# eggbothat3.net
KiCad netlist of a schematic drawn in EAGLE
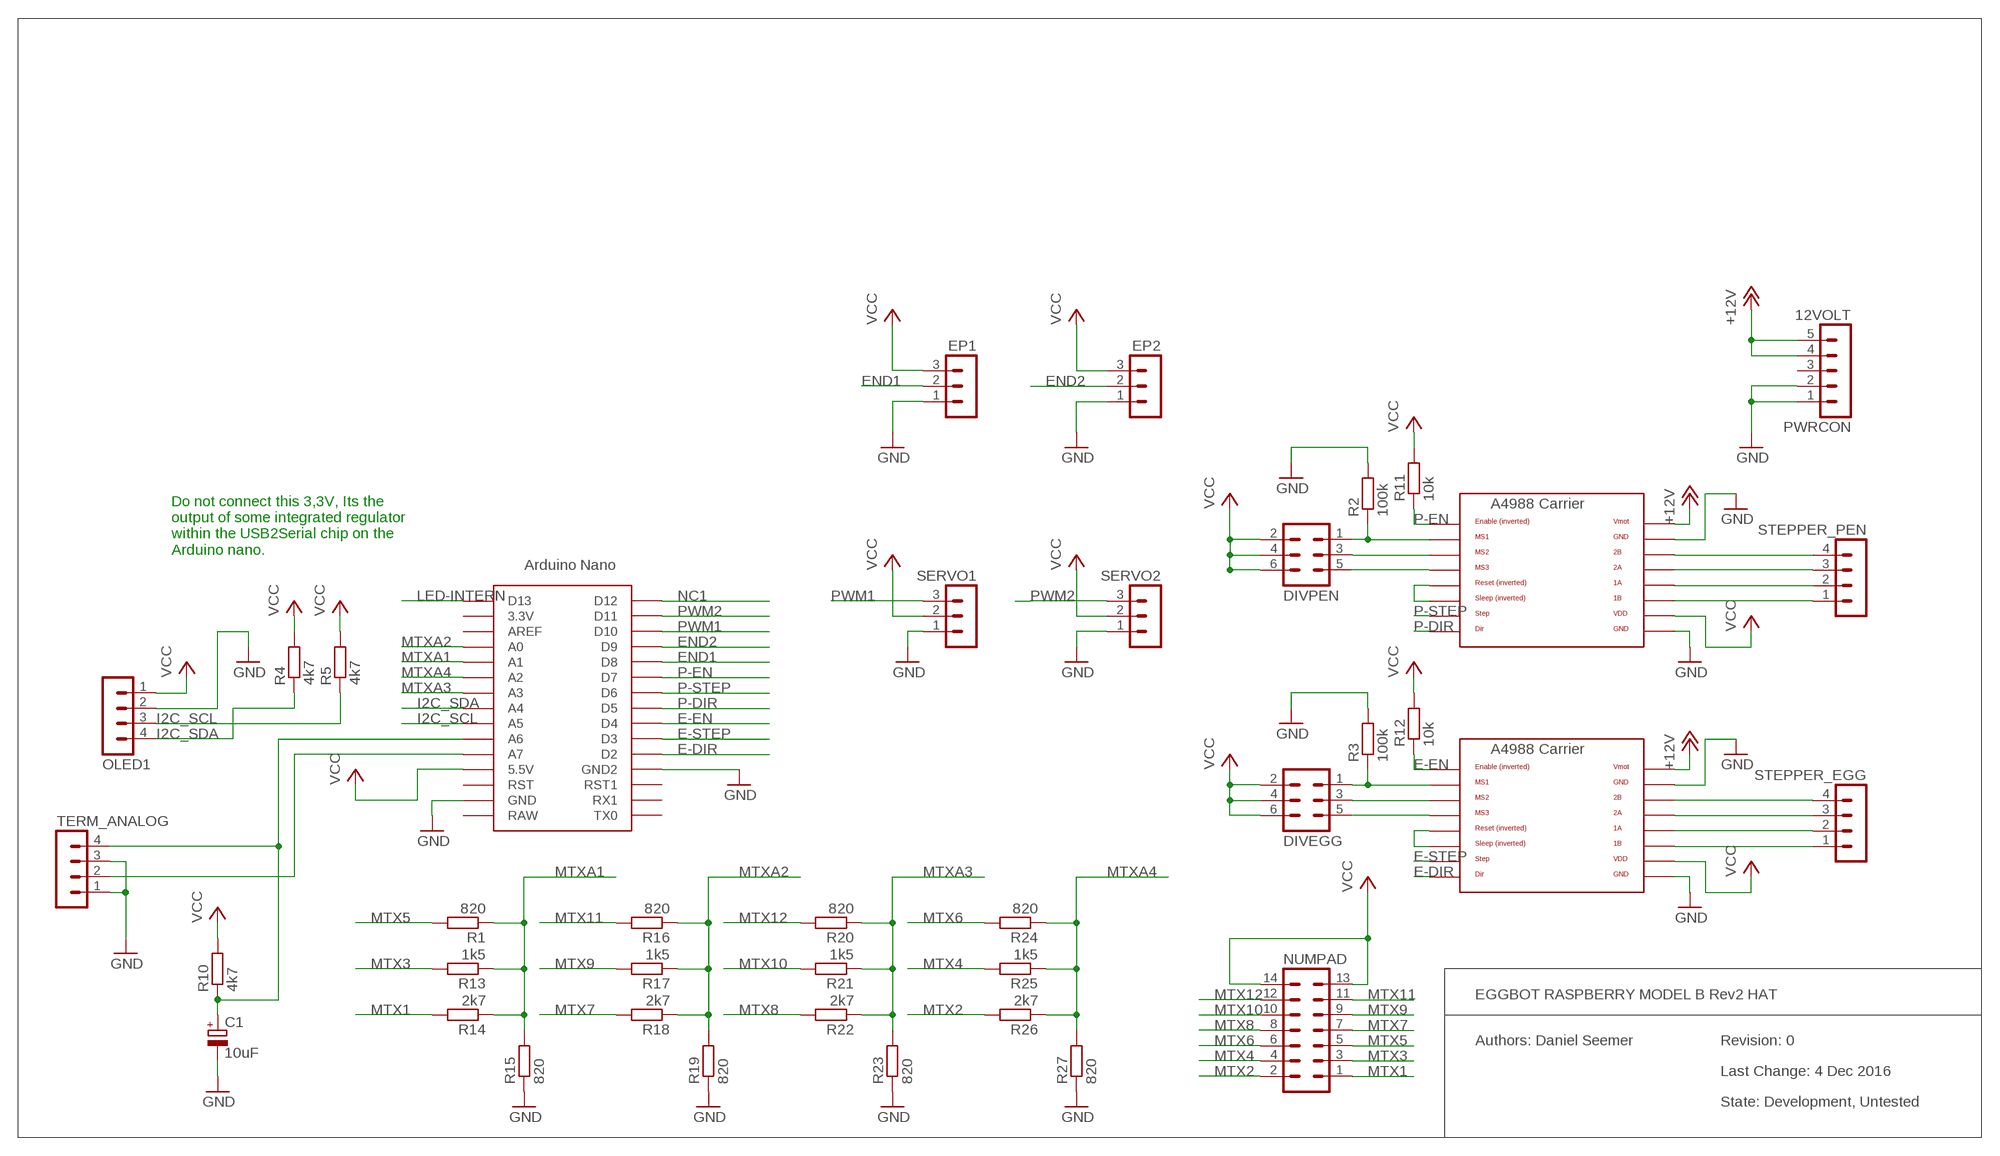
[diagram p0: schematic, sheet 1]

(export (version "E")
  (design (tool "Eeschema 10.0.6"))
  (components
    (comp (ref "12VOLT")
      (value "PWRCON")
      (footprint "eagle-import:MA05-1")
      (libsource (lib "eagle-import") (part "MA05-1"))
    )
    (comp (ref "C1")
      (value "10uF")
      (footprint "eagle-import:E2,5-5")
      (libsource (lib "eagle-import") (part "CPOL-EUE2.5-5"))
    )
    (comp (ref "DIVEGG")
      (value "MA03-2")
      (footprint "eagle-import:MA03-2")
      (libsource (lib "eagle-import") (part "MA03-2"))
    )
    (comp (ref "DIVPEN")
      (value "MA03-2")
      (footprint "eagle-import:MA03-2")
      (libsource (lib "eagle-import") (part "MA03-2"))
    )
    (comp (ref "EP1")
      (value "MA03-1")
      (footprint "eagle-import:MA03-1")
      (libsource (lib "eagle-import") (part "MA03-1"))
    )
    (comp (ref "EP2")
      (value "MA03-1")
      (footprint "eagle-import:MA03-1")
      (libsource (lib "eagle-import") (part "MA03-1"))
    )
    (comp (ref "NUMPAD")
      (value "MA07-2")
      (footprint "eagle-import:MA07-2")
      (libsource (lib "eagle-import") (part "MA07-2"))
    )
    (comp (ref "OLED1")
      (value "MA04-1")
      (footprint "eagle-import:MA04-1")
      (libsource (lib "eagle-import") (part "MA04-1"))
    )
    (comp (ref "R1")
      (value "820")
      (footprint "eagle-import:R1206")
      (libsource (lib "eagle-import") (part "R-EU_R1206"))
    )
    (comp (ref "R2")
      (value "100k")
      (footprint "eagle-import:R1206")
      (libsource (lib "eagle-import") (part "R-EU_R1206"))
    )
    (comp (ref "R3")
      (value "100k")
      (footprint "eagle-import:R1206")
      (libsource (lib "eagle-import") (part "R-EU_R1206"))
    )
    (comp (ref "R4")
      (value "4k7")
      (footprint "eagle-import:R1206")
      (libsource (lib "eagle-import") (part "R-EU_R1206"))
    )
    (comp (ref "R5")
      (value "4k7")
      (footprint "eagle-import:R1206")
      (libsource (lib "eagle-import") (part "R-EU_R1206"))
    )
    (comp (ref "R10")
      (value "4k7")
      (footprint "eagle-import:R1206")
      (libsource (lib "eagle-import") (part "R-EU_R1206"))
    )
    (comp (ref "R11")
      (value "10k")
      (footprint "eagle-import:R1206")
      (libsource (lib "eagle-import") (part "R-EU_R1206"))
    )
    (comp (ref "R12")
      (value "10k")
      (footprint "eagle-import:R1206")
      (libsource (lib "eagle-import") (part "R-EU_R1206"))
    )
    (comp (ref "R13")
      (value "1k5")
      (footprint "eagle-import:R1206")
      (libsource (lib "eagle-import") (part "R-EU_R1206"))
    )
    (comp (ref "R14")
      (value "2k7")
      (footprint "eagle-import:R1206")
      (libsource (lib "eagle-import") (part "R-EU_R1206"))
    )
    (comp (ref "R15")
      (value "820")
      (footprint "eagle-import:R1206")
      (libsource (lib "eagle-import") (part "R-EU_R1206"))
    )
    (comp (ref "R16")
      (value "820")
      (footprint "eagle-import:R1206")
      (libsource (lib "eagle-import") (part "R-EU_R1206"))
    )
    (comp (ref "R17")
      (value "1k5")
      (footprint "eagle-import:R1206")
      (libsource (lib "eagle-import") (part "R-EU_R1206"))
    )
    (comp (ref "R18")
      (value "2k7")
      (footprint "eagle-import:R1206")
      (libsource (lib "eagle-import") (part "R-EU_R1206"))
    )
    (comp (ref "R19")
      (value "820")
      (footprint "eagle-import:R1206")
      (libsource (lib "eagle-import") (part "R-EU_R1206"))
    )
    (comp (ref "R20")
      (value "820")
      (footprint "eagle-import:R1206")
      (libsource (lib "eagle-import") (part "R-EU_R1206"))
    )
    (comp (ref "R21")
      (value "1k5")
      (footprint "eagle-import:R1206")
      (libsource (lib "eagle-import") (part "R-EU_R1206"))
    )
    (comp (ref "R22")
      (value "2k7")
      (footprint "eagle-import:R1206")
      (libsource (lib "eagle-import") (part "R-EU_R1206"))
    )
    (comp (ref "R23")
      (value "820")
      (footprint "eagle-import:R1206")
      (libsource (lib "eagle-import") (part "R-EU_R1206"))
    )
    (comp (ref "R24")
      (value "820")
      (footprint "eagle-import:R1206")
      (libsource (lib "eagle-import") (part "R-EU_R1206"))
    )
    (comp (ref "R25")
      (value "1k5")
      (footprint "eagle-import:R1206")
      (libsource (lib "eagle-import") (part "R-EU_R1206"))
    )
    (comp (ref "R26")
      (value "2k7")
      (footprint "eagle-import:R1206")
      (libsource (lib "eagle-import") (part "R-EU_R1206"))
    )
    (comp (ref "R27")
      (value "820")
      (footprint "eagle-import:R1206")
      (libsource (lib "eagle-import") (part "R-EU_R1206"))
    )
    (comp (ref "SERVO1")
      (value "MA03-1")
      (footprint "eagle-import:MA03-1")
      (libsource (lib "eagle-import") (part "MA03-1"))
    )
    (comp (ref "SERVO2")
      (value "MA03-1")
      (footprint "eagle-import:MA03-1")
      (libsource (lib "eagle-import") (part "MA03-1"))
    )
    (comp (ref "STEPPER_EGG")
      (value "MA04-1")
      (footprint "eagle-import:MA04-1")
      (libsource (lib "eagle-import") (part "MA04-1"))
    )
    (comp (ref "STEPPER_PEN")
      (value "MA04-1")
      (footprint "eagle-import:MA04-1")
      (libsource (lib "eagle-import") (part "MA04-1"))
    )
    (comp (ref "TERM_ANALOG")
      (value "MA04-1")
      (footprint "eagle-import:MA04-1")
      (libsource (lib "eagle-import") (part "MA04-1"))
    )
    (comp (ref "U$1")
      (value "A4988BREAKOUT")
      (footprint "eagle-import:A4988BREAKOUT")
      (libsource (lib "eagle-import") (part "A4988BREAKOUT"))
    )
    (comp (ref "U$2")
      (value "A4988BREAKOUT")
      (footprint "eagle-import:A4988BREAKOUT")
      (libsource (lib "eagle-import") (part "A4988BREAKOUT"))
    )
    (comp (ref "U$4")
      (value "NANO")
      (footprint "eagle-import:NANO")
      (libsource (lib "eagle-import") (part "NANO"))
    )
  )
  (nets
    (net (code "1") (name "+12V") (class "Default")
      (node (ref "12VOLT") (pin "4") (pinfunction "4_4") (pintype "passive"))
      (node (ref "12VOLT") (pin "5") (pinfunction "5_5") (pintype "passive"))
      (node (ref "U$1") (pin "VMOT") (pinfunction "VMOT_VMOT") (pintype "power_in"))
      (node (ref "U$2") (pin "VMOT") (pinfunction "VMOT_VMOT") (pintype "power_in"))
    )
    (net (code "2") (name "E-DIR") (class "Default")
      (node (ref "U$2") (pin "DIR") (pinfunction "DIR_DIR") (pintype "input"))
      (node (ref "U$4") (pin "D2") (pinfunction "D2_D2") (pintype "bidirectional"))
    )
    (net (code "3") (name "E-EN") (class "Default")
      (node (ref "R12") (pin "1") (pinfunction "1_1") (pintype "passive"))
      (node (ref "U$2") (pin "EN") (pinfunction "EN_EN") (pintype "input"))
      (node (ref "U$4") (pin "D4") (pinfunction "D4_D4") (pintype "bidirectional"))
    )
    (net (code "4") (name "E-STEP") (class "Default")
      (node (ref "U$2") (pin "STEP") (pinfunction "STEP_STEP") (pintype "input"))
      (node (ref "U$4") (pin "D3") (pinfunction "D3_D3") (pintype "bidirectional"))
    )
    (net (code "5") (name "END1") (class "Default")
      (node (ref "EP1") (pin "2") (pinfunction "2_2") (pintype "passive"))
      (node (ref "U$4") (pin "D8") (pinfunction "D8_D8") (pintype "bidirectional"))
    )
    (net (code "6") (name "END2") (class "Default")
      (node (ref "EP2") (pin "2") (pinfunction "2_2") (pintype "passive"))
      (node (ref "U$4") (pin "D9") (pinfunction "D9_D9") (pintype "bidirectional"))
    )
    (net (code "7") (name "GND") (class "Default")
      (node (ref "12VOLT") (pin "1") (pinfunction "1_1") (pintype "passive"))
      (node (ref "12VOLT") (pin "2") (pinfunction "2_2") (pintype "passive"))
      (node (ref "C1") (pin "-") (pinfunction "-_-") (pintype "passive"))
      (node (ref "EP1") (pin "1") (pinfunction "1_1") (pintype "passive"))
      (node (ref "EP2") (pin "1") (pinfunction "1_1") (pintype "passive"))
      (node (ref "OLED1") (pin "2") (pinfunction "2_2") (pintype "passive"))
      (node (ref "R15") (pin "1") (pinfunction "1_1") (pintype "passive"))
      (node (ref "R19") (pin "1") (pinfunction "1_1") (pintype "passive"))
      (node (ref "R2") (pin "2") (pinfunction "2_2") (pintype "passive"))
      (node (ref "R23") (pin "1") (pinfunction "1_1") (pintype "passive"))
      (node (ref "R27") (pin "1") (pinfunction "1_1") (pintype "passive"))
      (node (ref "R3") (pin "2") (pinfunction "2_2") (pintype "passive"))
      (node (ref "SERVO1") (pin "1") (pinfunction "1_1") (pintype "passive"))
      (node (ref "SERVO2") (pin "1") (pinfunction "1_1") (pintype "passive"))
      (node (ref "TERM_ANALOG") (pin "1") (pinfunction "1_1") (pintype "passive"))
      (node (ref "TERM_ANALOG") (pin "3") (pinfunction "3_3") (pintype "passive"))
      (node (ref "U$1") (pin "GND") (pinfunction "GND_GND") (pintype "power_in"))
      (node (ref "U$1") (pin "GND@0") (pinfunction "GND_GND@0") (pintype "power_in"))
      (node (ref "U$2") (pin "GND") (pinfunction "GND_GND") (pintype "power_in"))
      (node (ref "U$2") (pin "GND@0") (pinfunction "GND_GND@0") (pintype "power_in"))
      (node (ref "U$4") (pin "GND") (pinfunction "GND_GND") (pintype "bidirectional"))
      (node (ref "U$4") (pin "GND1") (pinfunction "GND2_GND1") (pintype "bidirectional"))
    )
    (net (code "8") (name "I2C_SCL") (class "Default")
      (node (ref "OLED1") (pin "3") (pinfunction "3_3") (pintype "passive"))
      (node (ref "R5") (pin "1") (pinfunction "1_1") (pintype "passive"))
      (node (ref "U$4") (pin "A5") (pinfunction "A5_A5") (pintype "bidirectional"))
    )
    (net (code "9") (name "I2C_SDA") (class "Default")
      (node (ref "OLED1") (pin "4") (pinfunction "4_4") (pintype "passive"))
      (node (ref "R4") (pin "1") (pinfunction "1_1") (pintype "passive"))
      (node (ref "U$4") (pin "A4") (pinfunction "A4_A4") (pintype "bidirectional"))
    )
    (net (code "10") (name "LED-INTERN") (class "Default")
      (node (ref "U$4") (pin "D13") (pinfunction "D13_D13") (pintype "bidirectional"))
    )
    (net (code "11") (name "MTX1") (class "Default")
      (node (ref "NUMPAD") (pin "1") (pinfunction "1_1") (pintype "passive"))
      (node (ref "R14") (pin "2") (pinfunction "2_2") (pintype "passive"))
    )
    (net (code "12") (name "MTX2") (class "Default")
      (node (ref "NUMPAD") (pin "2") (pinfunction "2_2") (pintype "passive"))
      (node (ref "R26") (pin "2") (pinfunction "2_2") (pintype "passive"))
    )
    (net (code "13") (name "MTX3") (class "Default")
      (node (ref "NUMPAD") (pin "3") (pinfunction "3_3") (pintype "passive"))
      (node (ref "R13") (pin "2") (pinfunction "2_2") (pintype "passive"))
    )
    (net (code "14") (name "MTX4") (class "Default")
      (node (ref "NUMPAD") (pin "4") (pinfunction "4_4") (pintype "passive"))
      (node (ref "R25") (pin "2") (pinfunction "2_2") (pintype "passive"))
    )
    (net (code "15") (name "MTX5") (class "Default")
      (node (ref "NUMPAD") (pin "5") (pinfunction "5_5") (pintype "passive"))
      (node (ref "R1") (pin "2") (pinfunction "2_2") (pintype "passive"))
    )
    (net (code "16") (name "MTX6") (class "Default")
      (node (ref "NUMPAD") (pin "6") (pinfunction "6_6") (pintype "passive"))
      (node (ref "R24") (pin "2") (pinfunction "2_2") (pintype "passive"))
    )
    (net (code "17") (name "MTX7") (class "Default")
      (node (ref "NUMPAD") (pin "7") (pinfunction "7_7") (pintype "passive"))
      (node (ref "R18") (pin "2") (pinfunction "2_2") (pintype "passive"))
    )
    (net (code "18") (name "MTX8") (class "Default")
      (node (ref "NUMPAD") (pin "8") (pinfunction "8_8") (pintype "passive"))
      (node (ref "R22") (pin "2") (pinfunction "2_2") (pintype "passive"))
    )
    (net (code "19") (name "MTX9") (class "Default")
      (node (ref "NUMPAD") (pin "9") (pinfunction "9_9") (pintype "passive"))
      (node (ref "R17") (pin "2") (pinfunction "2_2") (pintype "passive"))
    )
    (net (code "20") (name "MTX10") (class "Default")
      (node (ref "NUMPAD") (pin "10") (pinfunction "10_10") (pintype "passive"))
      (node (ref "R21") (pin "2") (pinfunction "2_2") (pintype "passive"))
    )
    (net (code "21") (name "MTX11") (class "Default")
      (node (ref "NUMPAD") (pin "11") (pinfunction "11_11") (pintype "passive"))
      (node (ref "R16") (pin "2") (pinfunction "2_2") (pintype "passive"))
    )
    (net (code "22") (name "MTX12") (class "Default")
      (node (ref "NUMPAD") (pin "12") (pinfunction "12_12") (pintype "passive"))
      (node (ref "R20") (pin "2") (pinfunction "2_2") (pintype "passive"))
    )
    (net (code "23") (name "MTXA1") (class "Default")
      (node (ref "R1") (pin "1") (pinfunction "1_1") (pintype "passive"))
      (node (ref "R13") (pin "1") (pinfunction "1_1") (pintype "passive"))
      (node (ref "R14") (pin "1") (pinfunction "1_1") (pintype "passive"))
      (node (ref "R15") (pin "2") (pinfunction "2_2") (pintype "passive"))
      (node (ref "U$4") (pin "A1") (pinfunction "A1_A1") (pintype "bidirectional"))
    )
    (net (code "24") (name "MTXA2") (class "Default")
      (node (ref "R16") (pin "1") (pinfunction "1_1") (pintype "passive"))
      (node (ref "R17") (pin "1") (pinfunction "1_1") (pintype "passive"))
      (node (ref "R18") (pin "1") (pinfunction "1_1") (pintype "passive"))
      (node (ref "R19") (pin "2") (pinfunction "2_2") (pintype "passive"))
      (node (ref "U$4") (pin "A0") (pinfunction "A0_A0") (pintype "bidirectional"))
    )
    (net (code "25") (name "MTXA3") (class "Default")
      (node (ref "R20") (pin "1") (pinfunction "1_1") (pintype "passive"))
      (node (ref "R21") (pin "1") (pinfunction "1_1") (pintype "passive"))
      (node (ref "R22") (pin "1") (pinfunction "1_1") (pintype "passive"))
      (node (ref "R23") (pin "2") (pinfunction "2_2") (pintype "passive"))
      (node (ref "U$4") (pin "A3") (pinfunction "A3_A3") (pintype "bidirectional"))
    )
    (net (code "26") (name "MTXA4") (class "Default")
      (node (ref "R24") (pin "1") (pinfunction "1_1") (pintype "passive"))
      (node (ref "R25") (pin "1") (pinfunction "1_1") (pintype "passive"))
      (node (ref "R26") (pin "1") (pinfunction "1_1") (pintype "passive"))
      (node (ref "R27") (pin "2") (pinfunction "2_2") (pintype "passive"))
      (node (ref "U$4") (pin "A2") (pinfunction "A2_A2") (pintype "bidirectional"))
    )
    (net (code "27") (name "NC1") (class "Default")
      (node (ref "U$4") (pin "D12") (pinfunction "D12_D12") (pintype "bidirectional"))
    )
    (net (code "28") (name "Net-(C1-Pad+)") (class "Default")
      (node (ref "C1") (pin "+") (pinfunction "+_+") (pintype "passive"))
      (node (ref "R10") (pin "1") (pinfunction "1_1") (pintype "passive"))
      (node (ref "TERM_ANALOG") (pin "4") (pinfunction "4_4") (pintype "passive"))
      (node (ref "U$4") (pin "A6") (pinfunction "A6_A6") (pintype "bidirectional"))
    )
    (net (code "29") (name "Net-(DIVEGG-Pad1)") (class "Default")
      (node (ref "DIVEGG") (pin "1") (pinfunction "1_1") (pintype "passive"))
      (node (ref "R3") (pin "1") (pinfunction "1_1") (pintype "passive"))
      (node (ref "U$2") (pin "MS1") (pinfunction "MS1_MS1") (pintype "input"))
    )
    (net (code "30") (name "Net-(DIVEGG-Pad3)") (class "Default")
      (node (ref "DIVEGG") (pin "3") (pinfunction "3_3") (pintype "passive"))
      (node (ref "U$2") (pin "MS2") (pinfunction "MS2_MS2") (pintype "input"))
    )
    (net (code "31") (name "Net-(DIVEGG-Pad5)") (class "Default")
      (node (ref "DIVEGG") (pin "5") (pinfunction "5_5") (pintype "passive"))
      (node (ref "U$2") (pin "MS3") (pinfunction "MS3_MS3") (pintype "input"))
    )
    (net (code "32") (name "Net-(DIVPEN-Pad1)") (class "Default")
      (node (ref "DIVPEN") (pin "1") (pinfunction "1_1") (pintype "passive"))
      (node (ref "R2") (pin "1") (pinfunction "1_1") (pintype "passive"))
      (node (ref "U$1") (pin "MS1") (pinfunction "MS1_MS1") (pintype "input"))
    )
    (net (code "33") (name "Net-(DIVPEN-Pad3)") (class "Default")
      (node (ref "DIVPEN") (pin "3") (pinfunction "3_3") (pintype "passive"))
      (node (ref "U$1") (pin "MS2") (pinfunction "MS2_MS2") (pintype "input"))
    )
    (net (code "34") (name "Net-(DIVPEN-Pad5)") (class "Default")
      (node (ref "DIVPEN") (pin "5") (pinfunction "5_5") (pintype "passive"))
      (node (ref "U$1") (pin "MS3") (pinfunction "MS3_MS3") (pintype "input"))
    )
    (net (code "35") (name "Net-(STEPPER_EGG-Pad1)") (class "Default")
      (node (ref "STEPPER_EGG") (pin "1") (pinfunction "1_1") (pintype "passive"))
      (node (ref "U$2") (pin "1B") (pinfunction "1B_1B") (pintype "output"))
    )
    (net (code "36") (name "Net-(STEPPER_EGG-Pad2)") (class "Default")
      (node (ref "STEPPER_EGG") (pin "2") (pinfunction "2_2") (pintype "passive"))
      (node (ref "U$2") (pin "1A") (pinfunction "1A_1A") (pintype "output"))
    )
    (net (code "37") (name "Net-(STEPPER_EGG-Pad3)") (class "Default")
      (node (ref "STEPPER_EGG") (pin "3") (pinfunction "3_3") (pintype "passive"))
      (node (ref "U$2") (pin "2A") (pinfunction "2A_2A") (pintype "output"))
    )
    (net (code "38") (name "Net-(STEPPER_EGG-Pad4)") (class "Default")
      (node (ref "STEPPER_EGG") (pin "4") (pinfunction "4_4") (pintype "passive"))
      (node (ref "U$2") (pin "2B") (pinfunction "2B_2B") (pintype "output"))
    )
    (net (code "39") (name "Net-(STEPPER_PEN-Pad1)") (class "Default")
      (node (ref "STEPPER_PEN") (pin "1") (pinfunction "1_1") (pintype "passive"))
      (node (ref "U$1") (pin "1B") (pinfunction "1B_1B") (pintype "output"))
    )
    (net (code "40") (name "Net-(STEPPER_PEN-Pad2)") (class "Default")
      (node (ref "STEPPER_PEN") (pin "2") (pinfunction "2_2") (pintype "passive"))
      (node (ref "U$1") (pin "1A") (pinfunction "1A_1A") (pintype "output"))
    )
    (net (code "41") (name "Net-(STEPPER_PEN-Pad3)") (class "Default")
      (node (ref "STEPPER_PEN") (pin "3") (pinfunction "3_3") (pintype "passive"))
      (node (ref "U$1") (pin "2A") (pinfunction "2A_2A") (pintype "output"))
    )
    (net (code "42") (name "Net-(STEPPER_PEN-Pad4)") (class "Default")
      (node (ref "STEPPER_PEN") (pin "4") (pinfunction "4_4") (pintype "passive"))
      (node (ref "U$1") (pin "2B") (pinfunction "2B_2B") (pintype "output"))
    )
    (net (code "43") (name "Net-(TERM_ANALOG-Pad2)") (class "Default")
      (node (ref "TERM_ANALOG") (pin "2") (pinfunction "2_2") (pintype "passive"))
      (node (ref "U$4") (pin "A7") (pinfunction "A7_A7") (pintype "bidirectional"))
    )
    (net (code "44") (name "Net-(U$1-SLEEP)") (class "Default")
      (node (ref "U$1") (pin "RST") (pinfunction "RST_RST") (pintype "input"))
      (node (ref "U$1") (pin "SLP") (pinfunction "SLEEP_SLP") (pintype "input"))
    )
    (net (code "45") (name "Net-(U$2-SLEEP)") (class "Default")
      (node (ref "U$2") (pin "RST") (pinfunction "RST_RST") (pintype "input"))
      (node (ref "U$2") (pin "SLP") (pinfunction "SLEEP_SLP") (pintype "input"))
    )
    (net (code "46") (name "P-DIR") (class "Default")
      (node (ref "U$1") (pin "DIR") (pinfunction "DIR_DIR") (pintype "input"))
      (node (ref "U$4") (pin "D5") (pinfunction "D5_D5") (pintype "bidirectional"))
    )
    (net (code "47") (name "P-EN") (class "Default")
      (node (ref "R11") (pin "1") (pinfunction "1_1") (pintype "passive"))
      (node (ref "U$1") (pin "EN") (pinfunction "EN_EN") (pintype "input"))
      (node (ref "U$4") (pin "D7") (pinfunction "D7_D7") (pintype "bidirectional"))
    )
    (net (code "48") (name "P-STEP") (class "Default")
      (node (ref "U$1") (pin "STEP") (pinfunction "STEP_STEP") (pintype "input"))
      (node (ref "U$4") (pin "D6") (pinfunction "D6_D6") (pintype "bidirectional"))
    )
    (net (code "49") (name "PWM1") (class "Default")
      (node (ref "SERVO1") (pin "3") (pinfunction "3_3") (pintype "passive"))
      (node (ref "U$4") (pin "D10") (pinfunction "D10_D10") (pintype "bidirectional"))
    )
    (net (code "50") (name "PWM2") (class "Default")
      (node (ref "SERVO2") (pin "3") (pinfunction "3_3") (pintype "passive"))
      (node (ref "U$4") (pin "D11") (pinfunction "D11_D11") (pintype "bidirectional"))
    )
    (net (code "51") (name "VCC") (class "Default")
      (node (ref "DIVEGG") (pin "2") (pinfunction "2_2") (pintype "passive"))
      (node (ref "DIVEGG") (pin "4") (pinfunction "4_4") (pintype "passive"))
      (node (ref "DIVEGG") (pin "6") (pinfunction "6_6") (pintype "passive"))
      (node (ref "DIVPEN") (pin "2") (pinfunction "2_2") (pintype "passive"))
      (node (ref "DIVPEN") (pin "4") (pinfunction "4_4") (pintype "passive"))
      (node (ref "DIVPEN") (pin "6") (pinfunction "6_6") (pintype "passive"))
      (node (ref "EP1") (pin "3") (pinfunction "3_3") (pintype "passive"))
      (node (ref "EP2") (pin "3") (pinfunction "3_3") (pintype "passive"))
      (node (ref "NUMPAD") (pin "13") (pinfunction "13_13") (pintype "passive"))
      (node (ref "NUMPAD") (pin "14") (pinfunction "14_14") (pintype "passive"))
      (node (ref "OLED1") (pin "1") (pinfunction "1_1") (pintype "passive"))
      (node (ref "R10") (pin "2") (pinfunction "2_2") (pintype "passive"))
      (node (ref "R11") (pin "2") (pinfunction "2_2") (pintype "passive"))
      (node (ref "R12") (pin "2") (pinfunction "2_2") (pintype "passive"))
      (node (ref "R4") (pin "2") (pinfunction "2_2") (pintype "passive"))
      (node (ref "R5") (pin "2") (pinfunction "2_2") (pintype "passive"))
      (node (ref "SERVO1") (pin "2") (pinfunction "2_2") (pintype "passive"))
      (node (ref "SERVO2") (pin "2") (pinfunction "2_2") (pintype "passive"))
      (node (ref "U$1") (pin "VDD") (pinfunction "VDD_VDD") (pintype "power_in"))
      (node (ref "U$2") (pin "VDD") (pinfunction "VDD_VDD") (pintype "power_in"))
      (node (ref "U$4") (pin "5V") (pinfunction "5.5V_5V") (pintype "bidirectional"))
    )
    (net (code "52") (name "unconnected-(12VOLT-Pad3)") (class "Default")
      (node (ref "12VOLT") (pin "3") (pinfunction "3_3") (pintype "passive"))
    )
    (net (code "53") (name "unconnected-(U$4-Pad3.3V)") (class "Default")
      (node (ref "U$4") (pin "3.3V") (pinfunction "3.3V_3.3V") (pintype "bidirectional"))
    )
    (net (code "54") (name "unconnected-(U$4-PadAREF)") (class "Default")
      (node (ref "U$4") (pin "AREF") (pinfunction "AREF_AREF") (pintype "bidirectional"))
    )
    (net (code "55") (name "unconnected-(U$4-PadRAW)") (class "Default")
      (node (ref "U$4") (pin "RAW") (pinfunction "RAW_RAW") (pintype "bidirectional"))
    )
    (net (code "56") (name "unconnected-(U$4-PadRST)") (class "Default")
      (node (ref "U$4") (pin "RST") (pinfunction "RST_RST") (pintype "bidirectional"))
    )
    (net (code "57") (name "unconnected-(U$4-PadRST1)") (class "Default")
      (node (ref "U$4") (pin "RST1") (pinfunction "RST1_RST1") (pintype "bidirectional"))
    )
    (net (code "58") (name "unconnected-(U$4-PadRX1)") (class "Default")
      (node (ref "U$4") (pin "RX1") (pinfunction "RX1_RX1") (pintype "bidirectional"))
    )
    (net (code "59") (name "unconnected-(U$4-PadTX0)") (class "Default")
      (node (ref "U$4") (pin "TX0") (pinfunction "TX0_TX0") (pintype "bidirectional"))
    )
  )
)
